# APCBaby8_UtilityBoard.net
KiCad netlist of a schematic drawn in EAGLE
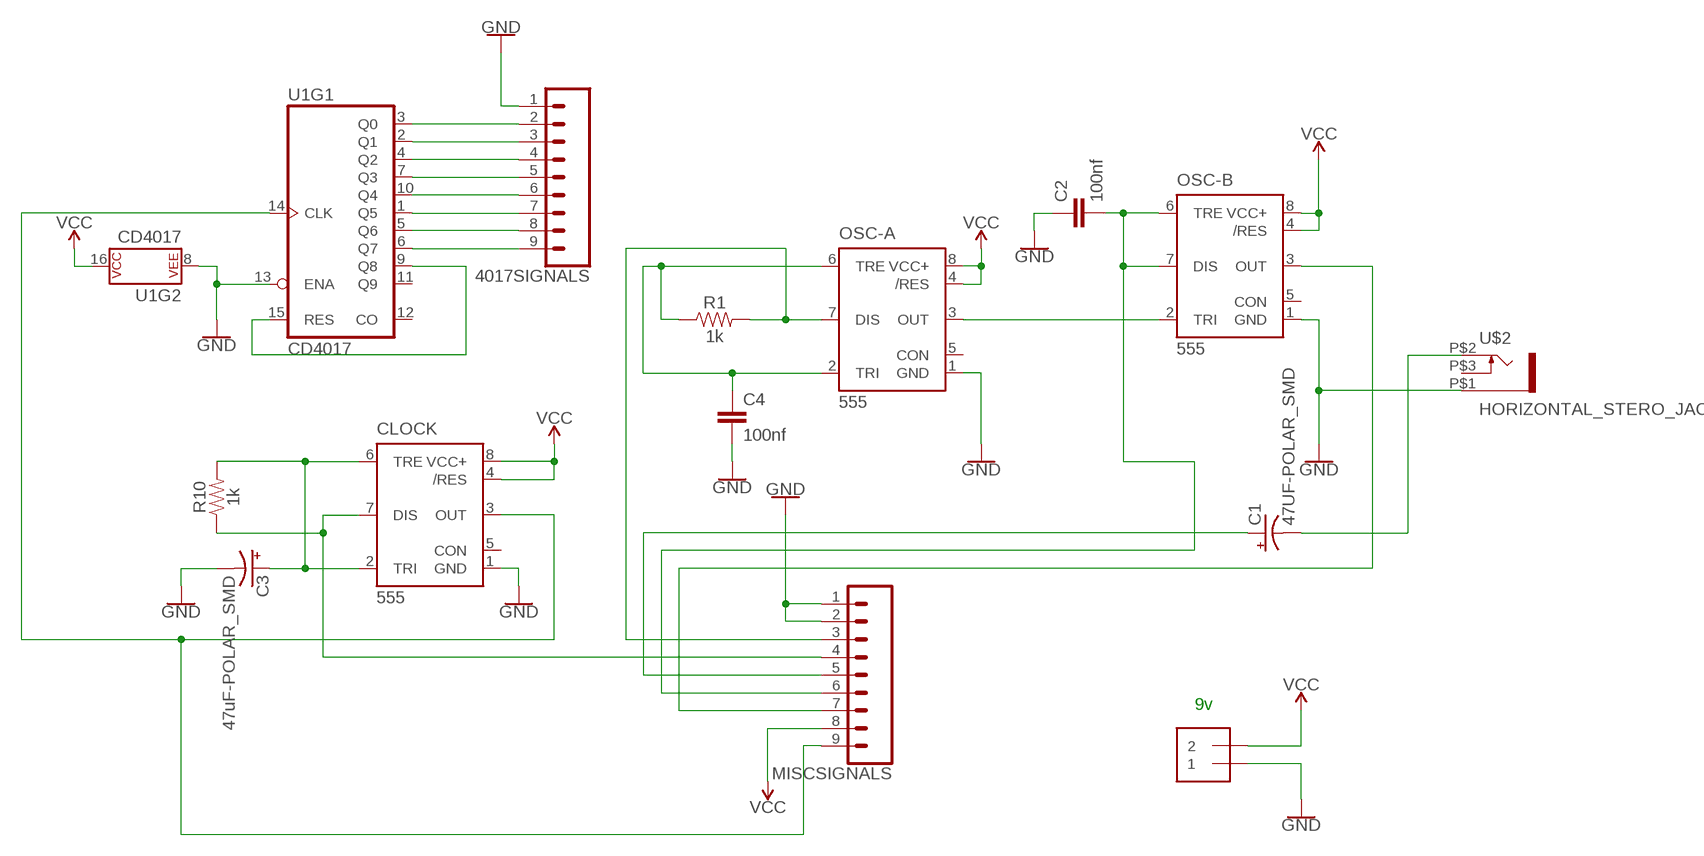
[diagram p0: schematic, sheet 1]

(export (version "E")
  (design (tool "Eeschema 10.0.6"))
  (components
    (comp (ref "9V")
      (value "9v")
      (footprint "eagle-import:1X2-3.5MM")
      (libsource (lib "eagle-import") (part "1X2-3.5MM"))
    )
    (comp (ref "4017SIGNALS")
      (value "CONN_09LONGPADS")
      (footprint "eagle-import:1X09_LONGPADS")
      (libsource (lib "eagle-import") (part "CONN_09LONGPADS"))
    )
    (comp (ref "C1")
      (value "47UF-POLAR_SMD")
      (footprint "eagle-import:PANASONIC_D")
      (libsource (lib "eagle-import") (part "47UF-POLAR-PANASONIC_D-50V-20%"))
    )
    (comp (ref "C2")
      (value "100nf")
      (footprint "eagle-import:0805")
      (libsource (lib "eagle-import") (part "0.33UF/330NF-0805-50V-10%"))
    )
    (comp (ref "C3")
      (value "47uF-POLAR_SMD")
      (footprint "eagle-import:PANASONIC_D")
      (libsource (lib "eagle-import") (part "47UF-POLAR-PANASONIC_D-35V-20%"))
    )
    (comp (ref "C4")
      (value "100nf")
      (footprint "eagle-import:0805")
      (libsource (lib "eagle-import") (part "0.33UF/330NF-0805-50V-10%"))
    )
    (comp (ref "CLOCK")
      (value "555")
      (footprint "eagle-import:DIP08-KIT")
      (libsource (lib "eagle-import") (part "555KIT"))
    )
    (comp (ref "MISCSIGNALS")
      (value "CONN_09LONGPADS")
      (footprint "eagle-import:1X09_LONGPADS")
      (libsource (lib "eagle-import") (part "CONN_09LONGPADS"))
    )
    (comp (ref "OSC-A")
      (value "555")
      (footprint "eagle-import:DIP08-KIT")
      (libsource (lib "eagle-import") (part "555KIT"))
    )
    (comp (ref "OSC-B")
      (value "555")
      (footprint "eagle-import:DIP08-KIT")
      (libsource (lib "eagle-import") (part "555KIT"))
    )
    (comp (ref "R1")
      (value "1k")
      (footprint "eagle-import:0805")
      (libsource (lib "eagle-import") (part "0.3OHM-0805-1/8W-1%"))
    )
    (comp (ref "R10")
      (value "1k")
      (footprint "eagle-import:0805")
      (libsource (lib "eagle-import") (part "0.3OHM-0805-1/8W-1%"))
    )
    (comp (ref "U$2")
      (value "HORIZONTAL_STERO_JACK")
      (footprint "eagle-import:HORIZONTAL_STEREO_JACK")
      (libsource (lib "eagle-import") (part "HORIZONTAL_STERO_JACK"))
    )
    (comp (ref "U1")
      (value "CD4017")
      (footprint "eagle-import:DIP16")
      (libsource (lib "eagle-import") (part "CD4017"))
    )
  )
  (nets
    (net (code "1") (name "GND") (class "Default")
      (node (ref "4017SIGNALS") (pin "1") (pinfunction "1_1") (pintype "passive"))
      (node (ref "9V") (pin "1") (pinfunction "1_1") (pintype "passive"))
      (node (ref "C2") (pin "1") (pinfunction "1_1") (pintype "passive"))
      (node (ref "C3") (pin "-") (pinfunction "-_-") (pintype "passive"))
      (node (ref "C4") (pin "2") (pinfunction "2_2") (pintype "passive"))
      (node (ref "CLOCK") (pin "1") (pinfunction "GND_1") (pintype "power_in"))
      (node (ref "MISCSIGNALS") (pin "1") (pinfunction "1_1") (pintype "passive"))
      (node (ref "MISCSIGNALS") (pin "2") (pinfunction "2_2") (pintype "passive"))
      (node (ref "OSC-A") (pin "1") (pinfunction "GND_1") (pintype "power_in"))
      (node (ref "OSC-B") (pin "1") (pinfunction "GND_1") (pintype "power_in"))
      (node (ref "U$2") (pin "P$1") (pinfunction "1_P$1") (pintype "passive"))
      (node (ref "U1") (pin "13") (pinfunction "ENA_13") (pintype "input"))
      (node (ref "U1") (pin "8") (pinfunction "P$V-_8") (pintype "bidirectional"))
    )
    (net (code "2") (name "Net-(C1-Pad+)") (class "Default")
      (node (ref "C1") (pin "+") (pinfunction "+_+") (pintype "passive"))
      (node (ref "MISCSIGNALS") (pin "5") (pinfunction "5_5") (pintype "passive"))
    )
    (net (code "3") (name "Net-(CLOCK-DIS)") (class "Default")
      (node (ref "CLOCK") (pin "7") (pinfunction "DIS_7") (pintype "input"))
      (node (ref "MISCSIGNALS") (pin "4") (pinfunction "4_4") (pintype "passive"))
      (node (ref "R10") (pin "1") (pinfunction "1_1") (pintype "passive"))
    )
    (net (code "4") (name "Net-(CLOCK-OUT)") (class "Default")
      (node (ref "CLOCK") (pin "3") (pinfunction "OUT_3") (pintype "output"))
      (node (ref "MISCSIGNALS") (pin "9") (pinfunction "9_9") (pintype "passive"))
      (node (ref "U1") (pin "14") (pinfunction "CLK_14") (pintype "input"))
    )
    (net (code "5") (name "Net-(CLOCK-TRE)") (class "Default")
      (node (ref "C3") (pin "+") (pinfunction "+_+") (pintype "passive"))
      (node (ref "CLOCK") (pin "2") (pinfunction "TRI_2") (pintype "input"))
      (node (ref "CLOCK") (pin "6") (pinfunction "TRE_6") (pintype "input"))
      (node (ref "R10") (pin "2") (pinfunction "2_2") (pintype "passive"))
    )
    (net (code "6") (name "Net-(OSC-A-DIS)") (class "Default")
      (node (ref "MISCSIGNALS") (pin "3") (pinfunction "3_3") (pintype "passive"))
      (node (ref "OSC-A") (pin "7") (pinfunction "DIS_7") (pintype "input"))
      (node (ref "R1") (pin "2") (pinfunction "2_2") (pintype "passive"))
    )
    (net (code "7") (name "Net-(OSC-A-OUT)") (class "Default")
      (node (ref "OSC-A") (pin "3") (pinfunction "OUT_3") (pintype "output"))
      (node (ref "OSC-B") (pin "2") (pinfunction "TRI_2") (pintype "input"))
    )
    (net (code "8") (name "Net-(OSC-A-TRE)") (class "Default")
      (node (ref "C4") (pin "1") (pinfunction "1_1") (pintype "passive"))
      (node (ref "OSC-A") (pin "2") (pinfunction "TRI_2") (pintype "input"))
      (node (ref "OSC-A") (pin "6") (pinfunction "TRE_6") (pintype "input"))
      (node (ref "R1") (pin "1") (pinfunction "1_1") (pintype "passive"))
    )
    (net (code "9") (name "Net-(OSC-B-DIS)") (class "Default")
      (node (ref "C2") (pin "2") (pinfunction "2_2") (pintype "passive"))
      (node (ref "MISCSIGNALS") (pin "6") (pinfunction "6_6") (pintype "passive"))
      (node (ref "OSC-B") (pin "6") (pinfunction "TRE_6") (pintype "input"))
      (node (ref "OSC-B") (pin "7") (pinfunction "DIS_7") (pintype "input"))
    )
    (net (code "10") (name "Net-(OSC-B-OUT)") (class "Default")
      (node (ref "MISCSIGNALS") (pin "7") (pinfunction "7_7") (pintype "passive"))
      (node (ref "OSC-B") (pin "3") (pinfunction "OUT_3") (pintype "output"))
    )
    (net (code "11") (name "Net-(U$2-2)") (class "Default")
      (node (ref "C1") (pin "-") (pinfunction "-_-") (pintype "passive"))
      (node (ref "U$2") (pin "P$2") (pinfunction "2_P$2") (pintype "passive"))
    )
    (net (code "12") (name "Net-(U1A-Q0)") (class "Default")
      (node (ref "4017SIGNALS") (pin "2") (pinfunction "2_2") (pintype "passive"))
      (node (ref "U1") (pin "3") (pinfunction "Q0_3") (pintype "output"))
    )
    (net (code "13") (name "Net-(U1A-Q1)") (class "Default")
      (node (ref "4017SIGNALS") (pin "3") (pinfunction "3_3") (pintype "passive"))
      (node (ref "U1") (pin "2") (pinfunction "Q1_2") (pintype "output"))
    )
    (net (code "14") (name "Net-(U1A-Q2)") (class "Default")
      (node (ref "4017SIGNALS") (pin "4") (pinfunction "4_4") (pintype "passive"))
      (node (ref "U1") (pin "4") (pinfunction "Q2_4") (pintype "output"))
    )
    (net (code "15") (name "Net-(U1A-Q3)") (class "Default")
      (node (ref "4017SIGNALS") (pin "5") (pinfunction "5_5") (pintype "passive"))
      (node (ref "U1") (pin "7") (pinfunction "Q3_7") (pintype "output"))
    )
    (net (code "16") (name "Net-(U1A-Q4)") (class "Default")
      (node (ref "4017SIGNALS") (pin "6") (pinfunction "6_6") (pintype "passive"))
      (node (ref "U1") (pin "10") (pinfunction "Q4_10") (pintype "output"))
    )
    (net (code "17") (name "Net-(U1A-Q5)") (class "Default")
      (node (ref "4017SIGNALS") (pin "7") (pinfunction "7_7") (pintype "passive"))
      (node (ref "U1") (pin "1") (pinfunction "Q5_1") (pintype "output"))
    )
    (net (code "18") (name "Net-(U1A-Q6)") (class "Default")
      (node (ref "4017SIGNALS") (pin "8") (pinfunction "8_8") (pintype "passive"))
      (node (ref "U1") (pin "5") (pinfunction "Q6_5") (pintype "output"))
    )
    (net (code "19") (name "Net-(U1A-Q7)") (class "Default")
      (node (ref "4017SIGNALS") (pin "9") (pinfunction "9_9") (pintype "passive"))
      (node (ref "U1") (pin "6") (pinfunction "Q7_6") (pintype "output"))
    )
    (net (code "20") (name "Net-(U1A-Q8)") (class "Default")
      (node (ref "U1") (pin "15") (pinfunction "RES_15") (pintype "input"))
      (node (ref "U1") (pin "9") (pinfunction "Q8_9") (pintype "output"))
    )
    (net (code "21") (name "VCC") (class "Default")
      (node (ref "9V") (pin "2") (pinfunction "2_2") (pintype "passive"))
      (node (ref "CLOCK") (pin "4") (pinfunction "/RES_4") (pintype "input"))
      (node (ref "CLOCK") (pin "8") (pinfunction "VCC+_8") (pintype "power_in"))
      (node (ref "MISCSIGNALS") (pin "8") (pinfunction "8_8") (pintype "passive"))
      (node (ref "OSC-A") (pin "4") (pinfunction "/RES_4") (pintype "input"))
      (node (ref "OSC-A") (pin "8") (pinfunction "VCC+_8") (pintype "power_in"))
      (node (ref "OSC-B") (pin "4") (pinfunction "/RES_4") (pintype "input"))
      (node (ref "OSC-B") (pin "8") (pinfunction "VCC+_8") (pintype "power_in"))
      (node (ref "U1") (pin "16") (pinfunction "P$V+_16") (pintype "bidirectional"))
    )
    (net (code "22") (name "unconnected-(CLOCK-CON-Pad5)") (class "Default")
      (node (ref "CLOCK") (pin "5") (pinfunction "CON_5") (pintype "input"))
    )
    (net (code "23") (name "unconnected-(OSC-A-CON-Pad5)") (class "Default")
      (node (ref "OSC-A") (pin "5") (pinfunction "CON_5") (pintype "input"))
    )
    (net (code "24") (name "unconnected-(OSC-B-CON-Pad5)") (class "Default")
      (node (ref "OSC-B") (pin "5") (pinfunction "CON_5") (pintype "input"))
    )
    (net (code "25") (name "unconnected-(U$2-3-PadP$3)") (class "Default")
      (node (ref "U$2") (pin "P$3") (pinfunction "3_P$3") (pintype "passive"))
    )
    (net (code "26") (name "unconnected-(U1A-CO-Pad12)") (class "Default")
      (node (ref "U1") (pin "12") (pinfunction "CO_12") (pintype "output"))
    )
    (net (code "27") (name "unconnected-(U1A-Q9-Pad11)") (class "Default")
      (node (ref "U1") (pin "11") (pinfunction "Q9_11") (pintype "output"))
    )
  )
)
